# beacon3v04.net
KiCad netlist of a schematic drawn in EAGLE
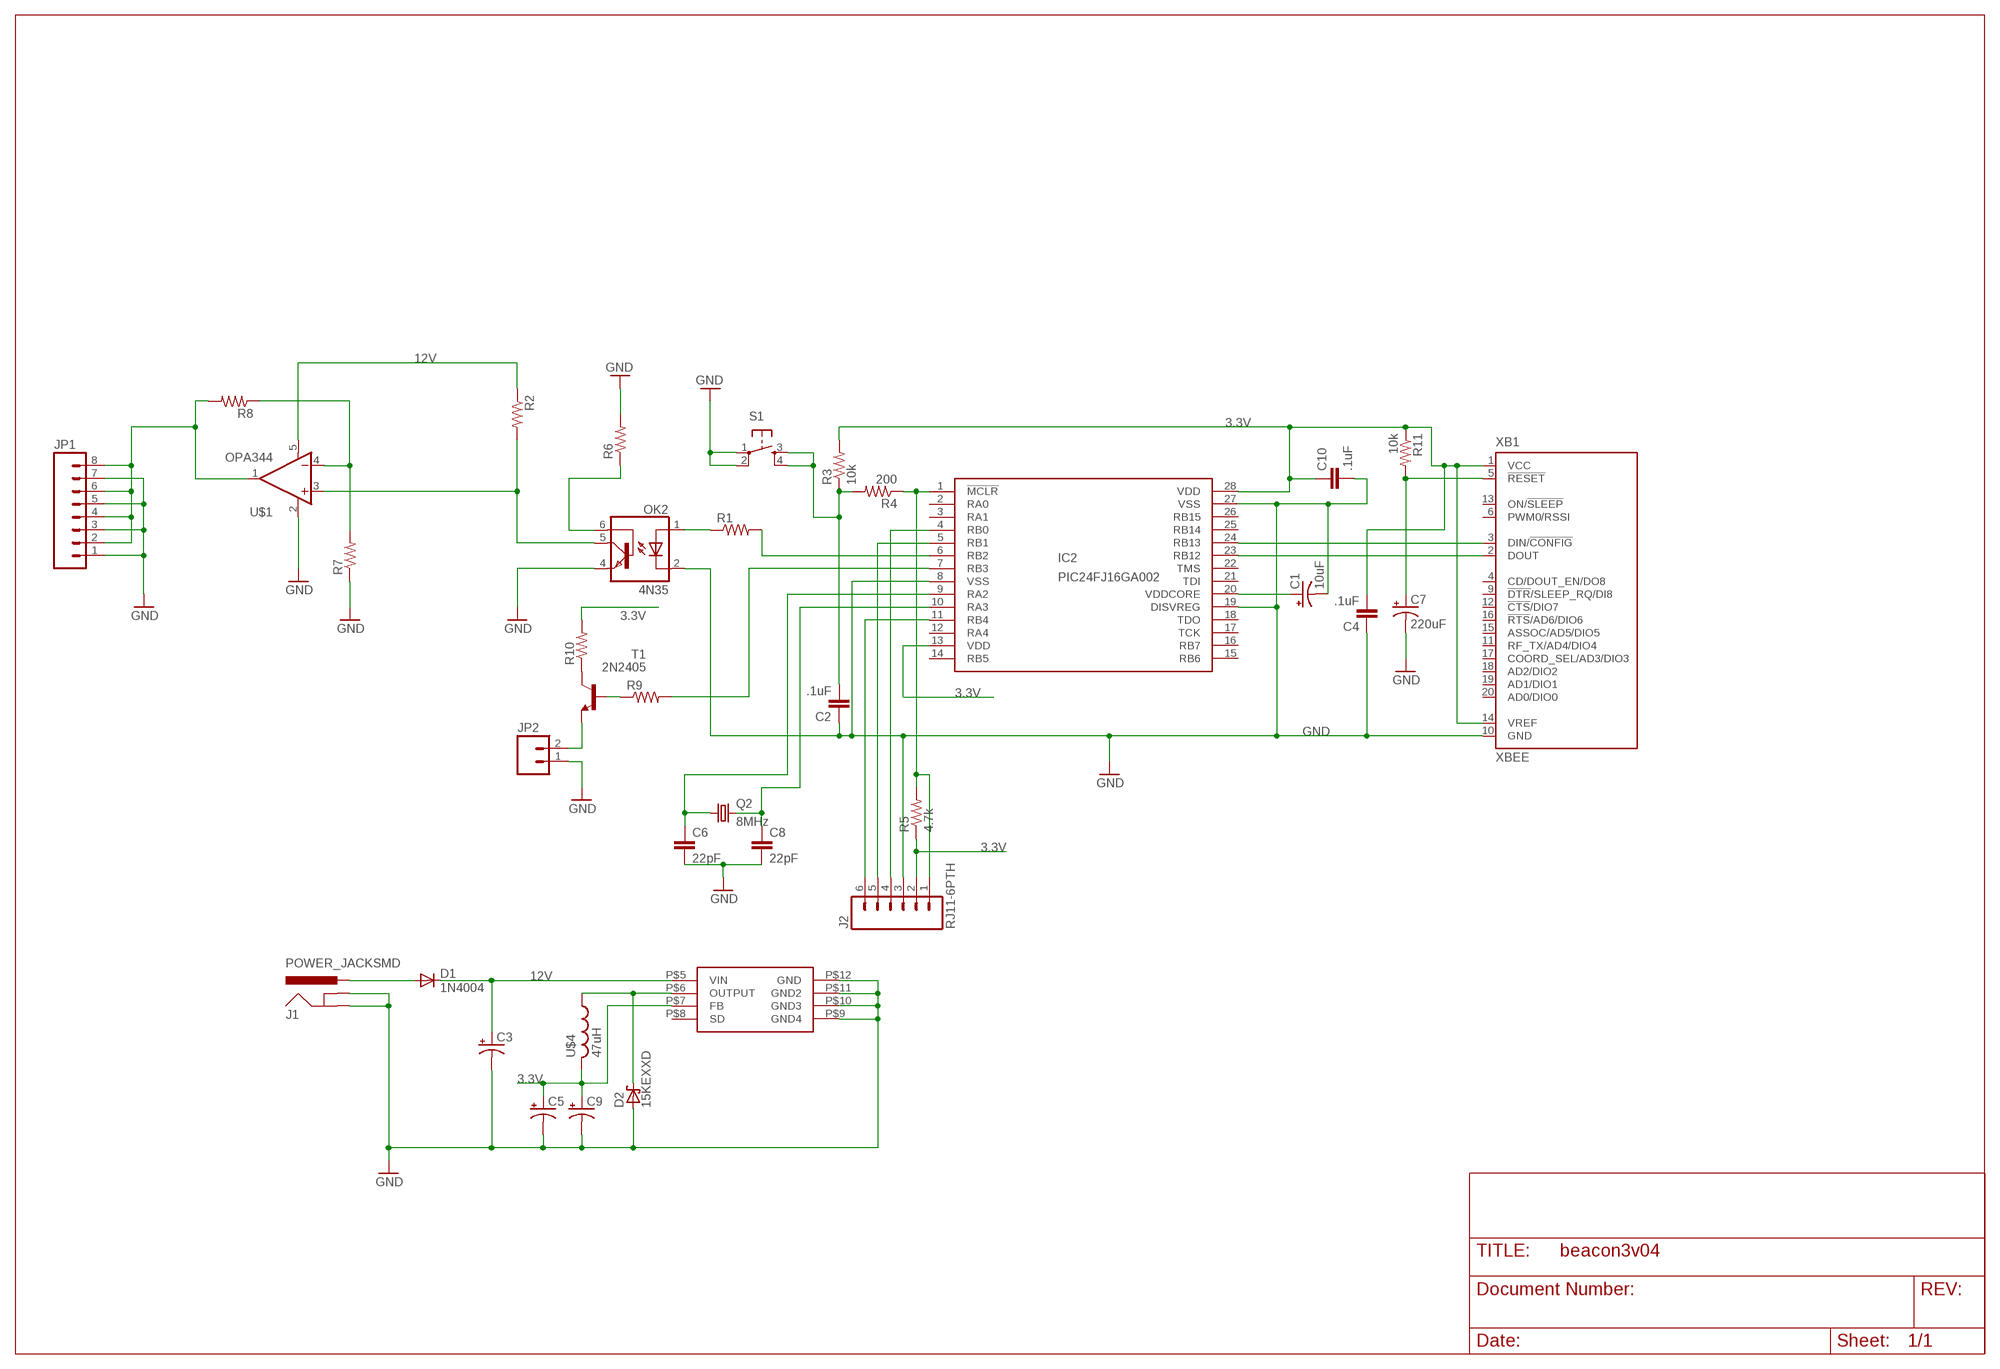
[diagram p0: schematic, sheet 1]

(export (version "E")
  (design (tool "Eeschema 10.0.6"))
  (components
    (comp (ref "C1")
      (value "10uF")
      (footprint "eagle-import:EIA3216")
      (libsource (lib "eagle-import") (part "CAP_POL1206"))
    )
    (comp (ref "C2")
      (value ".1uF")
      (footprint "eagle-import:C1206")
      (libsource (lib "eagle-import") (part "C-EUC1206"))
    )
    (comp (ref "C3")
      (value "CAP_POL1206")
      (footprint "eagle-import:EIA3216")
      (libsource (lib "eagle-import") (part "CAP_POL1206"))
    )
    (comp (ref "C4")
      (value ".1uF")
      (footprint "eagle-import:C1206")
      (libsource (lib "eagle-import") (part "C-EUC1206"))
    )
    (comp (ref "C5")
      (value "CAP_POL1206")
      (footprint "eagle-import:EIA3216")
      (libsource (lib "eagle-import") (part "CAP_POL1206"))
    )
    (comp (ref "C6")
      (value "22pF")
      (footprint "eagle-import:C1206")
      (libsource (lib "eagle-import") (part "C-EUC1206"))
    )
    (comp (ref "C7")
      (value "220uF")
      (footprint "eagle-import:EIA3216")
      (libsource (lib "eagle-import") (part "CAP_POL1206"))
    )
    (comp (ref "C8")
      (value "22pF")
      (footprint "eagle-import:C1206")
      (libsource (lib "eagle-import") (part "C-EUC1206"))
    )
    (comp (ref "C9")
      (value "CAP_POL1206")
      (footprint "eagle-import:EIA3216")
      (libsource (lib "eagle-import") (part "CAP_POL1206"))
    )
    (comp (ref "C10")
      (value ".1uF")
      (footprint "eagle-import:C1206")
      (libsource (lib "eagle-import") (part "C-EUC1206"))
    )
    (comp (ref "D1")
      (value "1N4004")
      (footprint "eagle-import:DO41-10")
      (libsource (lib "eagle-import") (part "1N4004"))
    )
    (comp (ref "D2")
      (value "15KEXXD")
      (footprint "eagle-import:DO201T15")
      (libsource (lib "eagle-import") (part "15KEXXD"))
    )
    (comp (ref "IC2")
      (value "PIC24FJ16GA002")
      (footprint "eagle-import:SO28W")
      (libsource (lib "eagle-import") (part "PIC24FJ16GA002"))
    )
    (comp (ref "J1")
      (value "POWER_JACKSMD")
      (footprint "eagle-import:POWER_JACK_SMD")
      (libsource (lib "eagle-import") (part "POWER_JACKSMD"))
    )
    (comp (ref "J2")
      (value "RJ11-6PTH")
      (footprint "eagle-import:RJ11-6")
      (libsource (lib "eagle-import") (part "RJ11-6PTH"))
    )
    (comp (ref "JP1")
      (value "M08LOCK")
      (footprint "eagle-import:1X08_LOCK")
      (libsource (lib "eagle-import") (part "M08LOCK"))
    )
    (comp (ref "JP2")
      (value "M02LOCK")
      (footprint "eagle-import:1X02_LOCK")
      (libsource (lib "eagle-import") (part "M02LOCK"))
    )
    (comp (ref "OK2")
      (value "4N35")
      (footprint "eagle-import:DIL06")
      (fields (field (name "MF") "FAIRCHILD SEMICONDUCTOR"))
      (libsource (lib "eagle-import") (part "4N35"))
    )
    (comp (ref "Q2")
      (value "8MHz")
      (footprint "eagle-import:HC49UP")
      (libsource (lib "eagle-import") (part "CRYSTALHC49UP"))
    )
    (comp (ref "R1")
      (value "RESISTOR1206")
      (footprint "eagle-import:1206")
      (libsource (lib "eagle-import") (part "RESISTOR1206"))
    )
    (comp (ref "R2")
      (value "RESISTOR1206")
      (footprint "eagle-import:1206")
      (libsource (lib "eagle-import") (part "RESISTOR1206"))
    )
    (comp (ref "R3")
      (value "10k")
      (footprint "eagle-import:1206")
      (libsource (lib "eagle-import") (part "RESISTOR1206"))
    )
    (comp (ref "R4")
      (value "200")
      (footprint "eagle-import:1206")
      (libsource (lib "eagle-import") (part "RESISTOR1206"))
    )
    (comp (ref "R5")
      (value "4.7k")
      (footprint "eagle-import:R1206")
      (libsource (lib "eagle-import") (part "R-US_R1206"))
    )
    (comp (ref "R6")
      (value "R-US_R1206")
      (footprint "eagle-import:R1206")
      (libsource (lib "eagle-import") (part "R-US_R1206"))
    )
    (comp (ref "R7")
      (value "RESISTOR1206")
      (footprint "eagle-import:1206")
      (libsource (lib "eagle-import") (part "RESISTOR1206"))
    )
    (comp (ref "R8")
      (value "RESISTOR1206")
      (footprint "eagle-import:1206")
      (libsource (lib "eagle-import") (part "RESISTOR1206"))
    )
    (comp (ref "R9")
      (value "R-US_R1206")
      (footprint "eagle-import:R1206")
      (libsource (lib "eagle-import") (part "R-US_R1206"))
    )
    (comp (ref "R10")
      (value "R-US_R1206")
      (footprint "eagle-import:R1206")
      (libsource (lib "eagle-import") (part "R-US_R1206"))
    )
    (comp (ref "R11")
      (value "10k")
      (footprint "eagle-import:1206")
      (libsource (lib "eagle-import") (part "RESISTOR1206"))
    )
    (comp (ref "S1")
      (value "TAC_SWITCHSMD")
      (footprint "eagle-import:TACTILE_SWITCH_SMD")
      (libsource (lib "eagle-import") (part "TAC_SWITCHSMD"))
    )
    (comp (ref "T1")
      (value "2N2405")
      (footprint "eagle-import:TO5")
      (libsource (lib "eagle-import") (part "2N2405"))
    )
    (comp (ref "U$1")
      (value "OPA344")
      (footprint "eagle-import:SOT23-5")
      (libsource (lib "eagle-import") (part "OPA344"))
    )
    (comp (ref "U$3")
      (value "BUCK1")
      (footprint "eagle-import:BUCK")
      (libsource (lib "eagle-import") (part "BUCK1"))
    )
    (comp (ref "U$4")
      (value "47uH")
      (footprint "eagle-import:BUCKINDUCTOR2")
      (libsource (lib "eagle-import") (part "BUCKINDUCTOR"))
    )
    (comp (ref "XB1")
      (value "XBEE")
      (footprint "eagle-import:XBEE")
      (fields (field (name "MPN") "XBP24-Z7UIT-004"))
      (libsource (lib "eagle-import") (part "XBEE"))
    )
  )
  (nets
    (net (code "1") (name "/3.3V") (class "Default")
      (node (ref "C10") (pin "1") (pinfunction "1_1") (pintype "passive"))
      (node (ref "C4") (pin "2") (pinfunction "2_2") (pintype "passive"))
      (node (ref "C5") (pin "A") (pinfunction "+_A") (pintype "passive"))
      (node (ref "C9") (pin "A") (pinfunction "+_A") (pintype "passive"))
      (node (ref "IC2") (pin "13") (pinfunction "VDD_13") (pintype "power_in"))
      (node (ref "IC2") (pin "28") (pinfunction "VDD_28") (pintype "power_in"))
      (node (ref "J2") (pin "2") (pinfunction "2_2") (pintype "passive"))
      (node (ref "R10") (pin "2") (pinfunction "2_2") (pintype "passive"))
      (node (ref "R11") (pin "1") (pinfunction "1_1") (pintype "passive"))
      (node (ref "R3") (pin "2") (pinfunction "2_2") (pintype "passive"))
      (node (ref "R5") (pin "1") (pinfunction "1_1") (pintype "passive"))
      (node (ref "U$3") (pin "P$7") (pinfunction "FB_P$7") (pintype "bidirectional"))
      (node (ref "U$4") (pin "P$2") (pinfunction "2_P$2") (pintype "passive"))
      (node (ref "XB1") (pin "1") (pinfunction "VCC_1") (pintype "power_in"))
      (node (ref "XB1") (pin "14") (pinfunction "VREF_14") (pintype "input"))
    )
    (net (code "2") (name "/12V") (class "Default")
      (node (ref "C3") (pin "A") (pinfunction "+_A") (pintype "passive"))
      (node (ref "D1") (pin "C") (pinfunction "C_C") (pintype "passive"))
      (node (ref "R2") (pin "1") (pinfunction "1_1") (pintype "passive"))
      (node (ref "U$1") (pin "5") (pinfunction "V+_5") (pintype "power_in"))
      (node (ref "U$3") (pin "P$5") (pinfunction "VIN_P$5") (pintype "bidirectional"))
    )
    (net (code "3") (name "GND") (class "Default")
      (node (ref "C1") (pin "C") (pinfunction "-_C") (pintype "passive"))
      (node (ref "C10") (pin "2") (pinfunction "2_2") (pintype "passive"))
      (node (ref "C2") (pin "1") (pinfunction "1_1") (pintype "passive"))
      (node (ref "C3") (pin "C") (pinfunction "-_C") (pintype "passive"))
      (node (ref "C4") (pin "1") (pinfunction "1_1") (pintype "passive"))
      (node (ref "C5") (pin "C") (pinfunction "-_C") (pintype "passive"))
      (node (ref "C6") (pin "2") (pinfunction "2_2") (pintype "passive"))
      (node (ref "C7") (pin "C") (pinfunction "-_C") (pintype "passive"))
      (node (ref "C8") (pin "2") (pinfunction "2_2") (pintype "passive"))
      (node (ref "C9") (pin "C") (pinfunction "-_C") (pintype "passive"))
      (node (ref "D2") (pin "A") (pinfunction "A_A") (pintype "passive"))
      (node (ref "IC2") (pin "19") (pinfunction "DISVREG_19") (pintype "passive"))
      (node (ref "IC2") (pin "27") (pinfunction "VSS_27") (pintype "power_in"))
      (node (ref "IC2") (pin "8") (pinfunction "VSS_8") (pintype "power_in"))
      (node (ref "J1") (pin "GND") (pinfunction "GNDBREAK_GND") (pintype "bidirectional"))
      (node (ref "J1") (pin "P$4") (pinfunction "GND_P$4") (pintype "bidirectional"))
      (node (ref "J2") (pin "3") (pinfunction "3_3") (pintype "passive"))
      (node (ref "JP1") (pin "1") (pinfunction "1_1") (pintype "passive"))
      (node (ref "JP1") (pin "3") (pinfunction "3_3") (pintype "passive"))
      (node (ref "JP1") (pin "5") (pinfunction "5_5") (pintype "passive"))
      (node (ref "JP1") (pin "7") (pinfunction "7_7") (pintype "passive"))
      (node (ref "JP2") (pin "1") (pinfunction "1_1") (pintype "passive"))
      (node (ref "OK2") (pin "2") (pinfunction "C_2") (pintype "passive"))
      (node (ref "OK2") (pin "4") (pinfunction "EMI_4") (pintype "passive"))
      (node (ref "R6") (pin "2") (pinfunction "2_2") (pintype "passive"))
      (node (ref "R7") (pin "1") (pinfunction "1_1") (pintype "passive"))
      (node (ref "S1") (pin "1") (pinfunction "1_1") (pintype "passive"))
      (node (ref "S1") (pin "2") (pinfunction "2_2") (pintype "passive"))
      (node (ref "U$1") (pin "2") (pinfunction "V-_2") (pintype "power_in"))
      (node (ref "U$3") (pin "P$10") (pinfunction "GND3_P$10") (pintype "bidirectional"))
      (node (ref "U$3") (pin "P$11") (pinfunction "GND2_P$11") (pintype "bidirectional"))
      (node (ref "U$3") (pin "P$12") (pinfunction "GND_P$12") (pintype "bidirectional"))
      (node (ref "U$3") (pin "P$9") (pinfunction "GND4_P$9") (pintype "bidirectional"))
      (node (ref "XB1") (pin "10") (pinfunction "GND_10") (pintype "power_in"))
    )
    (net (code "4") (name "Net-(C1-+)") (class "Default")
      (node (ref "C1") (pin "A") (pinfunction "+_A") (pintype "passive"))
      (node (ref "IC2") (pin "20") (pinfunction "VDDCORE_20") (pintype "power_in"))
    )
    (net (code "5") (name "Net-(C2-Pad2)") (class "Default")
      (node (ref "C2") (pin "2") (pinfunction "2_2") (pintype "passive"))
      (node (ref "R3") (pin "1") (pinfunction "1_1") (pintype "passive"))
      (node (ref "R4") (pin "2") (pinfunction "2_2") (pintype "passive"))
      (node (ref "S1") (pin "3") (pinfunction "3_3") (pintype "passive"))
      (node (ref "S1") (pin "4") (pinfunction "4_4") (pintype "passive"))
    )
    (net (code "6") (name "Net-(C7-+)") (class "Default")
      (node (ref "C7") (pin "A") (pinfunction "+_A") (pintype "passive"))
      (node (ref "R11") (pin "2") (pinfunction "2_2") (pintype "passive"))
      (node (ref "XB1") (pin "5") (pinfunction "~{RESET}_5") (pintype "input"))
    )
    (net (code "7") (name "Net-(IC2-RA2)") (class "Default")
      (node (ref "C6") (pin "1") (pinfunction "1_1") (pintype "passive"))
      (node (ref "IC2") (pin "9") (pinfunction "RA2_9") (pintype "bidirectional"))
      (node (ref "Q2") (pin "1") (pinfunction "1_1") (pintype "passive"))
    )
    (net (code "8") (name "Net-(IC2-RA3)") (class "Default")
      (node (ref "C8") (pin "1") (pinfunction "1_1") (pintype "passive"))
      (node (ref "IC2") (pin "10") (pinfunction "RA3_10") (pintype "bidirectional"))
      (node (ref "Q2") (pin "2") (pinfunction "2_2") (pintype "passive"))
    )
    (net (code "9") (name "Net-(IC2-RB0)") (class "Default")
      (node (ref "IC2") (pin "4") (pinfunction "RB0_4") (pintype "bidirectional"))
      (node (ref "J2") (pin "4") (pinfunction "4_4") (pintype "passive"))
    )
    (net (code "10") (name "Net-(IC2-RB1)") (class "Default")
      (node (ref "IC2") (pin "5") (pinfunction "RB1_5") (pintype "bidirectional"))
      (node (ref "J2") (pin "5") (pinfunction "5_5") (pintype "passive"))
    )
    (net (code "11") (name "Net-(IC2-RB2)") (class "Default")
      (node (ref "IC2") (pin "6") (pinfunction "RB2_6") (pintype "bidirectional"))
      (node (ref "R1") (pin "2") (pinfunction "2_2") (pintype "passive"))
    )
    (net (code "12") (name "Net-(IC2-RB3)") (class "Default")
      (node (ref "IC2") (pin "7") (pinfunction "RB3_7") (pintype "bidirectional"))
      (node (ref "R9") (pin "2") (pinfunction "2_2") (pintype "passive"))
    )
    (net (code "13") (name "Net-(IC2-RB4)") (class "Default")
      (node (ref "IC2") (pin "11") (pinfunction "RB4_11") (pintype "bidirectional"))
      (node (ref "J2") (pin "6") (pinfunction "6_6") (pintype "passive"))
    )
    (net (code "14") (name "Net-(IC2-RB12)") (class "Default")
      (node (ref "IC2") (pin "23") (pinfunction "RB12_23") (pintype "bidirectional"))
      (node (ref "XB1") (pin "2") (pinfunction "DOUT_2") (pintype "output"))
    )
    (net (code "15") (name "Net-(IC2-RB13)") (class "Default")
      (node (ref "IC2") (pin "24") (pinfunction "RB13_24") (pintype "bidirectional"))
      (node (ref "XB1") (pin "3") (pinfunction "DIN/~{CONFIG}_3") (pintype "input"))
    )
    (net (code "16") (name "Net-(IC2-~{MCLR})") (class "Default")
      (node (ref "IC2") (pin "1") (pinfunction "~{MCLR}_1") (pintype "bidirectional"))
      (node (ref "J2") (pin "1") (pinfunction "1_1") (pintype "passive"))
      (node (ref "R4") (pin "1") (pinfunction "1_1") (pintype "passive"))
      (node (ref "R5") (pin "2") (pinfunction "2_2") (pintype "passive"))
    )
    (net (code "17") (name "Net-(J1-PWR)") (class "Default")
      (node (ref "D1") (pin "A") (pinfunction "A_A") (pintype "passive"))
      (node (ref "J1") (pin "VIN0") (pinfunction "PWR_VIN0") (pintype "bidirectional"))
    )
    (net (code "18") (name "Net-(OK2-A)") (class "Default")
      (node (ref "OK2") (pin "1") (pinfunction "A_1") (pintype "passive"))
      (node (ref "R1") (pin "1") (pinfunction "1_1") (pintype "passive"))
    )
    (net (code "19") (name "Net-(OK2-BAS)") (class "Default")
      (node (ref "OK2") (pin "6") (pinfunction "BAS_6") (pintype "passive"))
      (node (ref "R6") (pin "1") (pinfunction "1_1") (pintype "passive"))
    )
    (net (code "20") (name "Net-(OK2-COL)") (class "Default")
      (node (ref "OK2") (pin "5") (pinfunction "COL_5") (pintype "passive"))
      (node (ref "R2") (pin "2") (pinfunction "2_2") (pintype "passive"))
      (node (ref "U$1") (pin "3") (pinfunction "+IN_3") (pintype "input"))
    )
    (net (code "21") (name "Net-(T1-B)") (class "Default")
      (node (ref "R9") (pin "1") (pinfunction "1_1") (pintype "passive"))
      (node (ref "T1") (pin "2") (pinfunction "B_2") (pintype "passive"))
    )
    (net (code "22") (name "Net-(T1-C)") (class "Default")
      (node (ref "R10") (pin "1") (pinfunction "1_1") (pintype "passive"))
      (node (ref "T1") (pin "3") (pinfunction "C_3") (pintype "passive"))
    )
    (net (code "23") (name "Net-(T1-E)") (class "Default")
      (node (ref "JP2") (pin "2") (pinfunction "2_2") (pintype "passive"))
      (node (ref "T1") (pin "1") (pinfunction "E_1") (pintype "passive"))
    )
    (net (code "24") (name "Net-(U$1--IN)") (class "Default")
      (node (ref "R7") (pin "2") (pinfunction "2_2") (pintype "passive"))
      (node (ref "R8") (pin "1") (pinfunction "1_1") (pintype "passive"))
      (node (ref "U$1") (pin "4") (pinfunction "-IN_4") (pintype "input"))
    )
    (net (code "25") (name "Net-(U$1-OUT)") (class "Default")
      (node (ref "JP1") (pin "2") (pinfunction "2_2") (pintype "passive"))
      (node (ref "JP1") (pin "4") (pinfunction "4_4") (pintype "passive"))
      (node (ref "JP1") (pin "6") (pinfunction "6_6") (pintype "passive"))
      (node (ref "JP1") (pin "8") (pinfunction "8_8") (pintype "passive"))
      (node (ref "R8") (pin "2") (pinfunction "2_2") (pintype "passive"))
      (node (ref "U$1") (pin "1") (pinfunction "OUT_1") (pintype "output"))
    )
    (net (code "26") (name "Net-(U$3-OUTPUT)") (class "Default")
      (node (ref "D2") (pin "C") (pinfunction "C_C") (pintype "passive"))
      (node (ref "U$3") (pin "P$6") (pinfunction "OUTPUT_P$6") (pintype "bidirectional"))
      (node (ref "U$4") (pin "P$1") (pinfunction "1_P$1") (pintype "passive"))
    )
    (net (code "27") (name "unconnected-(IC2-RA0-Pad2)") (class "Default")
      (node (ref "IC2") (pin "2") (pinfunction "RA0_2") (pintype "bidirectional"))
    )
    (net (code "28") (name "unconnected-(IC2-RA1-Pad3)") (class "Default")
      (node (ref "IC2") (pin "3") (pinfunction "RA1_3") (pintype "bidirectional"))
    )
    (net (code "29") (name "unconnected-(IC2-RA4-Pad12)") (class "Default")
      (node (ref "IC2") (pin "12") (pinfunction "RA4_12") (pintype "bidirectional"))
    )
    (net (code "30") (name "unconnected-(IC2-RB5-Pad14)") (class "Default")
      (node (ref "IC2") (pin "14") (pinfunction "RB5_14") (pintype "bidirectional"))
    )
    (net (code "31") (name "unconnected-(IC2-RB6-Pad15)") (class "Default")
      (node (ref "IC2") (pin "15") (pinfunction "RB6_15") (pintype "bidirectional"))
    )
    (net (code "32") (name "unconnected-(IC2-RB7-Pad16)") (class "Default")
      (node (ref "IC2") (pin "16") (pinfunction "RB7_16") (pintype "bidirectional"))
    )
    (net (code "33") (name "unconnected-(IC2-RB14-Pad25)") (class "Default")
      (node (ref "IC2") (pin "25") (pinfunction "RB14_25") (pintype "bidirectional"))
    )
    (net (code "34") (name "unconnected-(IC2-RB15-Pad26)") (class "Default")
      (node (ref "IC2") (pin "26") (pinfunction "RB15_26") (pintype "bidirectional"))
    )
    (net (code "35") (name "unconnected-(IC2-TCK-Pad17)") (class "Default")
      (node (ref "IC2") (pin "17") (pinfunction "TCK_17") (pintype "input"))
    )
    (net (code "36") (name "unconnected-(IC2-TDI-Pad21)") (class "Default")
      (node (ref "IC2") (pin "21") (pinfunction "TDI_21") (pintype "input"))
    )
    (net (code "37") (name "unconnected-(IC2-TDO-Pad18)") (class "Default")
      (node (ref "IC2") (pin "18") (pinfunction "TDO_18") (pintype "output"))
    )
    (net (code "38") (name "unconnected-(IC2-TMS-Pad22)") (class "Default")
      (node (ref "IC2") (pin "22") (pinfunction "TMS_22") (pintype "input"))
    )
    (net (code "39") (name "unconnected-(U$3-SD-PadP$8)") (class "Default")
      (node (ref "U$3") (pin "P$8") (pinfunction "SD_P$8") (pintype "bidirectional"))
    )
    (net (code "40") (name "unconnected-(XB1-AD0{slash}DIO0-Pad20)") (class "Default")
      (node (ref "XB1") (pin "20") (pinfunction "AD0/DIO0_20") (pintype "bidirectional"))
    )
    (net (code "41") (name "unconnected-(XB1-AD1{slash}DIO1-Pad19)") (class "Default")
      (node (ref "XB1") (pin "19") (pinfunction "AD1/DIO1_19") (pintype "bidirectional"))
    )
    (net (code "42") (name "unconnected-(XB1-AD2{slash}DIO2-Pad18)") (class "Default")
      (node (ref "XB1") (pin "18") (pinfunction "AD2/DIO2_18") (pintype "bidirectional"))
    )
    (net (code "43") (name "unconnected-(XB1-ASSOC{slash}AD5{slash}DIO5-Pad15)") (class "Default")
      (node (ref "XB1") (pin "15") (pinfunction "ASSOC/AD5/DIO5_15") (pintype "bidirectional"))
    )
    (net (code "44") (name "unconnected-(XB1-CD{slash}DOUT_EN{slash}DO8-Pad4)") (class "Default")
      (node (ref "XB1") (pin "4") (pinfunction "CD/DOUT_EN/DO8_4") (pintype "output"))
    )
    (net (code "45") (name "unconnected-(XB1-COORD_SEL{slash}AD3{slash}DIO3-Pad17)") (class "Default")
      (node (ref "XB1") (pin "17") (pinfunction "COORD_SEL/AD3/DIO3_17") (pintype "bidirectional"))
    )
    (net (code "46") (name "unconnected-(XB1-ON{slash}~{SLEEP}-Pad13)") (class "Default")
      (node (ref "XB1") (pin "13") (pinfunction "ON/~{SLEEP}_13") (pintype "output"))
    )
    (net (code "47") (name "unconnected-(XB1-PWM0{slash}RSSI-Pad6)") (class "Default")
      (node (ref "XB1") (pin "6") (pinfunction "PWM0/RSSI_6") (pintype "output"))
    )
    (net (code "48") (name "unconnected-(XB1-RF_TX{slash}AD4{slash}DIO4-Pad11)") (class "Default")
      (node (ref "XB1") (pin "11") (pinfunction "RF_TX/AD4/DIO4_11") (pintype "bidirectional"))
    )
    (net (code "49") (name "unconnected-(XB1-~{CTS}{slash}DIO7-Pad12)") (class "Default")
      (node (ref "XB1") (pin "12") (pinfunction "~{CTS}/DIO7_12") (pintype "bidirectional"))
    )
    (net (code "50") (name "unconnected-(XB1-~{DTR}{slash}SLEEP_RQ{slash}DI8-Pad9)") (class "Default")
      (node (ref "XB1") (pin "9") (pinfunction "~{DTR}/SLEEP_RQ/DI8_9") (pintype "bidirectional"))
    )
    (net (code "51") (name "unconnected-(XB1-~{RTS}{slash}AD6{slash}DIO6-Pad16)") (class "Default")
      (node (ref "XB1") (pin "16") (pinfunction "~{RTS}/AD6/DIO6_16") (pintype "bidirectional"))
    )
  )
)
